# ESP32_S3.net
KiCad netlist of a schematic drawn in Altium Designer
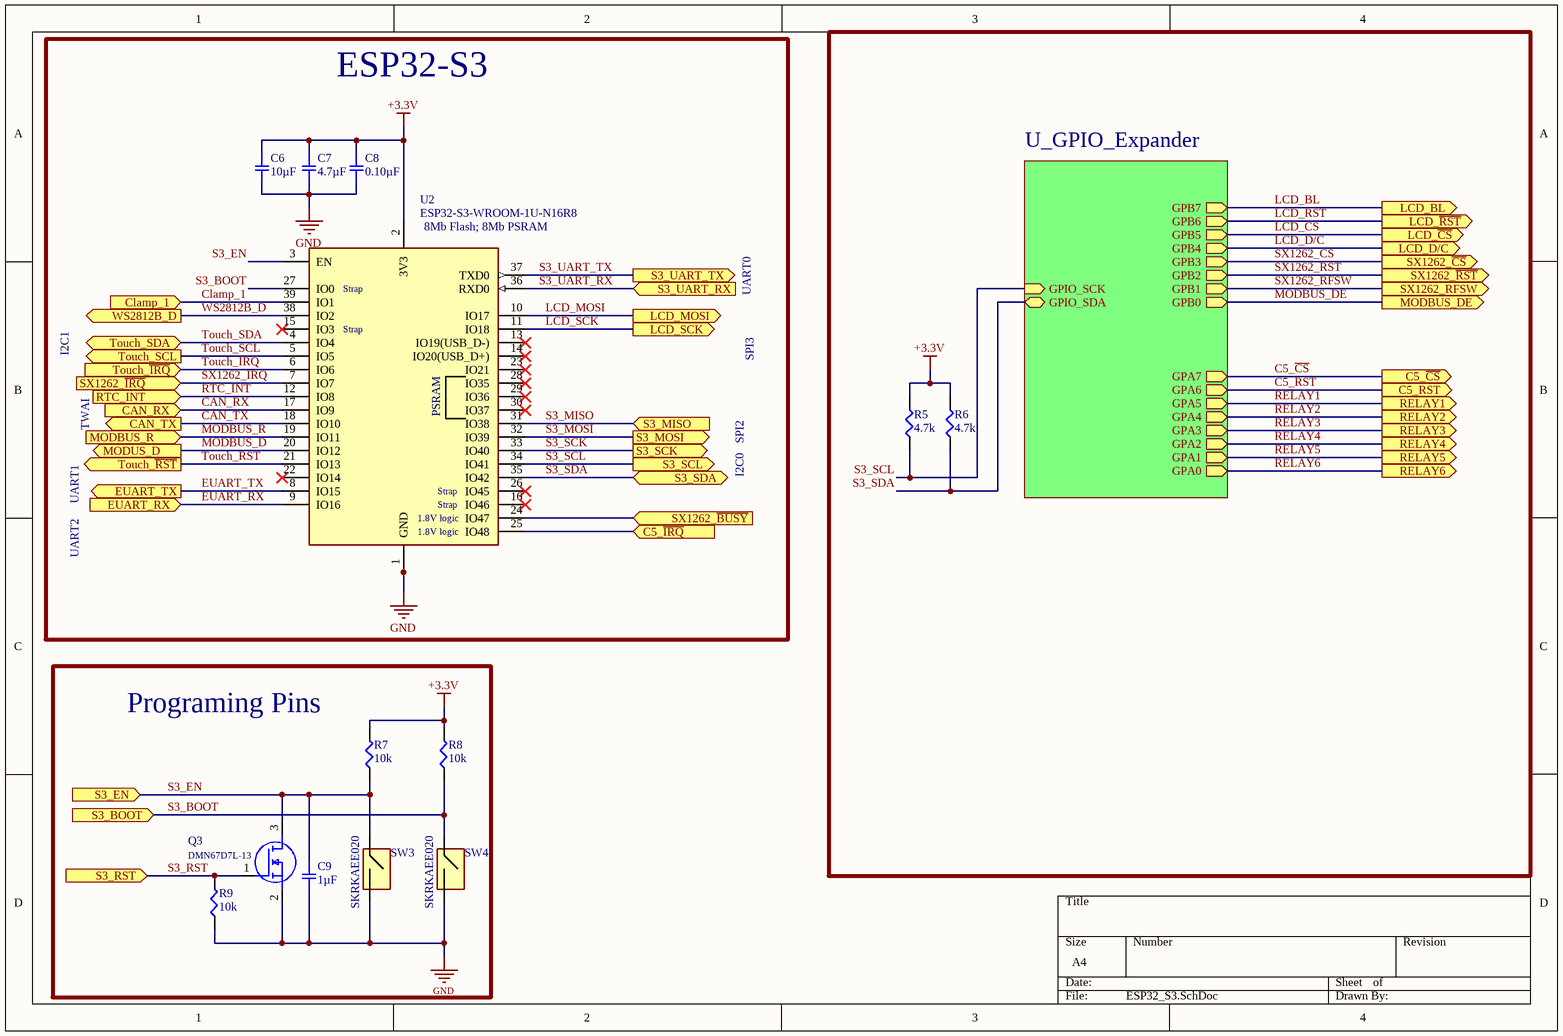
[diagram p0: ESP32_S3.SchDoc]

(export (version "E")
  (design (tool "Eeschema 10.0.6"))
  (components
    (comp (ref "C6")
      (value "10µF")
      (footprint "SMD-0603C")
      (description "CAP CER 10UF 6.3V X5R 0603")
      (fields
        (field (name "DIGI-KEY PART NUMBER") "490-10467-1-ND")
        (field (name "PART NUMBER") "GRM185R60J106ME15D")
      )
      (libsource (lib "capacitor_murata_0603") (part "GRM185R60J106ME15D"))
    )
    (comp (ref "C7")
      (value "4.7µF")
      (footprint "SMD-0402C")
      (description "CAP CER 4.7UF 6.3V X5R 0402")
      (fields
        (field (name "DIGI-KEY PART NUMBER") "490-13232-1-ND")
        (field (name "PART NUMBER") "GRM153R60J475ME15D")
      )
      (libsource (lib "capacitor_murata_0402") (part "GRM153R60J475ME15D"))
    )
    (comp (ref "C8")
      (value "0.10µF")
      (footprint "SMD-0402C")
      (description "CAP CER 0.1UF 16V X7R 0402")
      (fields
        (field (name "DIGI-KEY PART NUMBER") "490-4759-1-ND")
        (field (name "PART NUMBER") "GCM155R71C104KA55D")
      )
      (libsource (lib "capacitor_murata_0402") (part "GCM155R71C104KA55D"))
    )
    (comp (ref "C9")
      (value "1µF")
      (footprint "SMD-0402C")
      (description "CAP CER 1UF 10V X7S 0402")
      (fields
        (field (name "DIGI-KEY PART NUMBER") "490-13409-1-ND")
        (field (name "PART NUMBER") "GCM155C71A105KE38D")
      )
      (libsource (lib "capacitor_murata_0402") (part "GCM155C71A105KE38D"))
    )
    (comp (ref "Q3")
      (value "DMN67D7L-13")
      (footprint "SamacSys:DMN67D7L13")
      (description "MOSFET (N-Channel)")
      (fields (field (name "MOUSER PART NUMBER") "621-DMN67D7L-13"))
      (libsource (lib "*") (part "DMN67D7L-13"))
    )
    (comp (ref "R5")
      (value "4.7k")
      (footprint "SMD-0402-RES")
      (description "RES SMD 4.7K OHM 1% 1/10W 0402")
      (fields
        (field (name "PART NUMBER") "ERJ-2RKF4701X")
        (field (name "DIGI-KEY PART NUMBER") "P4.70KLCT-ND")
      )
      (libsource (lib "Panasonic_ERJ_0402") (part "ERJ-2RKF4701X"))
    )
    (comp (ref "R6")
      (value "4.7k")
      (footprint "SMD-0402-RES")
      (description "RES SMD 4.7K OHM 1% 1/10W 0402")
      (fields
        (field (name "PART NUMBER") "ERJ-2RKF4701X")
        (field (name "DIGI-KEY PART NUMBER") "P4.70KLCT-ND")
      )
      (libsource (lib "Panasonic_ERJ_0402") (part "ERJ-2RKF4701X"))
    )
    (comp (ref "R7")
      (value "10k")
      (footprint "SMD-0402-RES")
      (description "RES SMD 10K OHM 1% 1/10W 0402")
      (fields
        (field (name "PART NUMBER") "ERJ-2RKF1002X")
        (field (name "DIGI-KEY PART NUMBER") "P10.0KLCT-ND")
      )
      (libsource (lib "Panasonic_ERJ_0402") (part "ERJ-2RKF1002X"))
    )
    (comp (ref "R8")
      (value "10k")
      (footprint "SMD-0402-RES")
      (description "RES SMD 10K OHM 1% 1/10W 0402")
      (fields
        (field (name "PART NUMBER") "ERJ-2RKF1002X")
        (field (name "DIGI-KEY PART NUMBER") "P10.0KLCT-ND")
      )
      (libsource (lib "Panasonic_ERJ_0402") (part "ERJ-2RKF1002X"))
    )
    (comp (ref "R9")
      (value "10k")
      (footprint "SMD-0402-RES")
      (description "RES SMD 10K OHM 1% 1/10W 0402")
      (fields
        (field (name "PART NUMBER") "ERJ-2RKF1002X")
        (field (name "DIGI-KEY PART NUMBER") "P10.0KLCT-ND")
      )
      (libsource (lib "Panasonic_ERJ_0402") (part "ERJ-2RKF1002X"))
    )
    (comp (ref "SW3")
      (value "SKRKAEE020")
      (footprint "SKRKAEE020")
      (description "Tactile Switches 3.9x2.9x2.0mm 160gf Packaging Temp 80oC")
      (fields (field (name "MOUSER PART NUMBER") "688-SKRKAEE020"))
      (libsource (lib "SomoPowerPackControl") (part "SKRKAEE020"))
    )
    (comp (ref "SW4")
      (value "SKRKAEE020")
      (footprint "SKRKAEE020")
      (description "Tactile Switches 3.9x2.9x2.0mm 160gf Packaging Temp 80oC")
      (fields (field (name "MOUSER PART NUMBER") "688-SKRKAEE020"))
      (libsource (lib "SomoPowerPackControl") (part "SKRKAEE020"))
    )
    (comp (ref "U2")
      (value "ESP32-S3-WROOM-1U-N16R8")
      (footprint "SamacSys:ESP32S3WROOM1UN16R8")
      (fields (field (name "MOUSER PART NUMBER") "356-ESP32S3WM1UN16R8"))
      (libsource (lib "SamacSys") (part "ESP32-S3-WROOM-1U-N16R8"))
    )
  )
  (nets
    (net (code "1") (name "+3.3V") (class "Default")
      (node (ref "C6") (pin "1") (pinfunction "1_1") (pintype "passive"))
      (node (ref "C7") (pin "1") (pinfunction "1_1") (pintype "passive"))
      (node (ref "C8") (pin "1") (pinfunction "1_1") (pintype "passive"))
      (node (ref "R5") (pin "2") (pinfunction "2_2") (pintype "passive"))
      (node (ref "R6") (pin "2") (pinfunction "2_2") (pintype "passive"))
      (node (ref "R7") (pin "2") (pinfunction "2_2") (pintype "passive"))
      (node (ref "R8") (pin "2") (pinfunction "2_2") (pintype "passive"))
      (node (ref "U2") (pin "2") (pinfunction "3V3_2") (pintype "passive"))
    )
    (net (code "4") (name "/C5_~{IRQ}") (class "Default")
      (node (ref "U2") (pin "25") (pinfunction "IO48_25") (pintype "passive"))
    )
    (net (code "5") (name "/CAN_RX") (class "Default")
      (node (ref "U2") (pin "17") (pinfunction "IO9_17") (pintype "passive"))
    )
    (net (code "6") (name "/CAN_TX") (class "Default")
      (node (ref "U2") (pin "18") (pinfunction "IO10_18") (pintype "passive"))
    )
    (net (code "7") (name "/Clamp_1") (class "Default")
      (node (ref "U2") (pin "39") (pinfunction "IO1_39") (pintype "passive"))
    )
    (net (code "8") (name "/EUART_RX") (class "Default")
      (node (ref "U2") (pin "9") (pinfunction "IO16_9") (pintype "passive"))
    )
    (net (code "9") (name "/EUART_TX") (class "Default")
      (node (ref "U2") (pin "8") (pinfunction "IO15_8") (pintype "passive"))
    )
    (net (code "12") (name "/LCD_MOSI") (class "Default")
      (node (ref "U2") (pin "10") (pinfunction "IO17_10") (pintype "passive"))
    )
    (net (code "13") (name "/LCD_SCK") (class "Default")
      (node (ref "U2") (pin "11") (pinfunction "IO18_11") (pintype "passive"))
    )
    (net (code "16") (name "/MODBUS_D") (class "Default")
      (node (ref "U2") (pin "20") (pinfunction "IO12_20") (pintype "passive"))
    )
    (net (code "18") (name "/MODBUS_R") (class "Default")
      (node (ref "U2") (pin "19") (pinfunction "IO11_19") (pintype "passive"))
    )
    (net (code "25") (name "/RTC_INT") (class "Default")
      (node (ref "U2") (pin "12") (pinfunction "IO8_12") (pintype "passive"))
    )
    (net (code "26") (name "/S3_BOOT") (class "Default")
      (node (ref "R8") (pin "1") (pinfunction "1_1") (pintype "passive"))
      (node (ref "SW4") (pin "1") (pinfunction "1_1") (pintype "passive"))
      (node (ref "U2") (pin "27") (pinfunction "IO0_27") (pintype "passive"))
    )
    (net (code "27") (name "/S3_EN") (class "Default")
      (node (ref "C9") (pin "1") (pinfunction "1_1") (pintype "passive"))
      (node (ref "Q3") (pin "3") (pinfunction "D_3") (pintype "passive"))
      (node (ref "R7") (pin "1") (pinfunction "1_1") (pintype "passive"))
      (node (ref "SW3") (pin "1") (pinfunction "1_1") (pintype "passive"))
      (node (ref "U2") (pin "3") (pinfunction "EN_3") (pintype "passive"))
    )
    (net (code "28") (name "/S3_MISO") (class "Default")
      (node (ref "U2") (pin "31") (pinfunction "IO38_31") (pintype "passive"))
    )
    (net (code "29") (name "/S3_MOSI") (class "Default")
      (node (ref "U2") (pin "32") (pinfunction "IO39_32") (pintype "passive"))
    )
    (net (code "30") (name "/S3_RST") (class "Default")
      (node (ref "Q3") (pin "1") (pinfunction "G_1") (pintype "passive"))
      (node (ref "R9") (pin "2") (pinfunction "2_2") (pintype "passive"))
    )
    (net (code "31") (name "/S3_SCK") (class "Default")
      (node (ref "U2") (pin "33") (pinfunction "IO40_33") (pintype "passive"))
    )
    (net (code "32") (name "/S3_SCL") (class "Default")
      (node (ref "R5") (pin "1") (pinfunction "1_1") (pintype "passive"))
      (node (ref "U2") (pin "34") (pinfunction "IO41_34") (pintype "passive"))
    )
    (net (code "33") (name "/S3_SDA") (class "Default")
      (node (ref "R6") (pin "1") (pinfunction "1_1") (pintype "passive"))
      (node (ref "U2") (pin "35") (pinfunction "IO42_35") (pintype "passive"))
    )
    (net (code "34") (name "/S3_UART_RX") (class "Default")
      (node (ref "U2") (pin "36") (pinfunction "RXD0_36") (pintype "input"))
    )
    (net (code "35") (name "/S3_UART_TX") (class "Default")
      (node (ref "U2") (pin "37") (pinfunction "TXD0_37") (pintype "output"))
    )
    (net (code "37") (name "/SX1262_~{BUSY}") (class "Default")
      (node (ref "U2") (pin "24") (pinfunction "IO47_24") (pintype "passive"))
    )
    (net (code "39") (name "/SX1262_~{IRQ}") (class "Default")
      (node (ref "U2") (pin "7") (pinfunction "IO7_7") (pintype "passive"))
    )
    (net (code "41") (name "/Touch_SCL") (class "Default")
      (node (ref "U2") (pin "5") (pinfunction "IO5_5") (pintype "passive"))
    )
    (net (code "42") (name "/Touch_SDA") (class "Default")
      (node (ref "U2") (pin "4") (pinfunction "IO4_4") (pintype "passive"))
    )
    (net (code "43") (name "/Touch_~{IRQ}") (class "Default")
      (node (ref "U2") (pin "6") (pinfunction "IO6_6") (pintype "passive"))
    )
    (net (code "44") (name "/Touch_~{RST}") (class "Default")
      (node (ref "U2") (pin "21") (pinfunction "IO13_21") (pintype "passive"))
    )
    (net (code "45") (name "/WS2812B_D") (class "Default")
      (node (ref "U2") (pin "38") (pinfunction "IO2_38") (pintype "passive"))
    )
    (net (code "46") (name "GND") (class "Default")
      (node (ref "C6") (pin "2") (pinfunction "2_2") (pintype "passive"))
      (node (ref "C7") (pin "2") (pinfunction "2_2") (pintype "passive"))
      (node (ref "C8") (pin "2") (pinfunction "2_2") (pintype "passive"))
      (node (ref "C9") (pin "2") (pinfunction "2_2") (pintype "passive"))
      (node (ref "Q3") (pin "2") (pinfunction "S_2") (pintype "passive"))
      (node (ref "R9") (pin "1") (pinfunction "1_1") (pintype "passive"))
      (node (ref "SW3") (pin "2") (pinfunction "2_2") (pintype "passive"))
      (node (ref "SW4") (pin "2") (pinfunction "2_2") (pintype "passive"))
      (node (ref "U2") (pin "1") (pinfunction "GND_1") (pintype "passive"))
      (node (ref "U2") (pin "40") (pinfunction "GND_40") (pintype "passive"))
      (node (ref "U2") (pin "41") (pinfunction "GND_41") (pintype "passive"))
      (node (ref "U2") (pin "42") (pinfunction "GND_42") (pintype "passive"))
      (node (ref "U2") (pin "43") (pinfunction "GND_43") (pintype "passive"))
      (node (ref "U2") (pin "44") (pinfunction "GND_44") (pintype "passive"))
      (node (ref "U2") (pin "45") (pinfunction "GND_45") (pintype "passive"))
      (node (ref "U2") (pin "46") (pinfunction "GND_46") (pintype "passive"))
      (node (ref "U2") (pin "47") (pinfunction "GND_47") (pintype "passive"))
      (node (ref "U2") (pin "48") (pinfunction "GND_48") (pintype "passive"))
      (node (ref "U2") (pin "49") (pinfunction "GND_49") (pintype "passive"))
    )
    (net (code "47") (name "unconnected-(U2-IO3-Pad15)") (class "Default")
      (node (ref "U2") (pin "15") (pinfunction "IO3_15") (pintype "passive+no_connect"))
    )
    (net (code "48") (name "unconnected-(U2-IO14-Pad22)") (class "Default")
      (node (ref "U2") (pin "22") (pinfunction "IO14_22") (pintype "passive+no_connect"))
    )
    (net (code "49") (name "unconnected-(U2-IO19(USB_D-)-Pad13)") (class "Default")
      (node (ref "U2") (pin "13") (pinfunction "IO19(USB_D-)_13") (pintype "passive+no_connect"))
    )
    (net (code "50") (name "unconnected-(U2-IO20(USB_D+)-Pad14)") (class "Default")
      (node (ref "U2") (pin "14") (pinfunction "IO20(USB_D+)_14") (pintype "passive+no_connect"))
    )
    (net (code "51") (name "unconnected-(U2-IO21-Pad23)") (class "Default")
      (node (ref "U2") (pin "23") (pinfunction "IO21_23") (pintype "passive+no_connect"))
    )
    (net (code "52") (name "unconnected-(U2-IO35-Pad28)") (class "Default")
      (node (ref "U2") (pin "28") (pinfunction "IO35_28") (pintype "passive+no_connect"))
    )
    (net (code "53") (name "unconnected-(U2-IO36-Pad29)") (class "Default")
      (node (ref "U2") (pin "29") (pinfunction "IO36_29") (pintype "passive+no_connect"))
    )
    (net (code "54") (name "unconnected-(U2-IO37-Pad30)") (class "Default")
      (node (ref "U2") (pin "30") (pinfunction "IO37_30") (pintype "passive+no_connect"))
    )
    (net (code "55") (name "unconnected-(U2-IO45-Pad26)") (class "Default")
      (node (ref "U2") (pin "26") (pinfunction "IO45_26") (pintype "passive+no_connect"))
    )
    (net (code "56") (name "unconnected-(U2-IO46-Pad16)") (class "Default")
      (node (ref "U2") (pin "16") (pinfunction "IO46_16") (pintype "passive+no_connect"))
    )
  )
)
